# Sallen_key_bandpass.net
KiCad netlist of a schematic drawn in Altium Designer
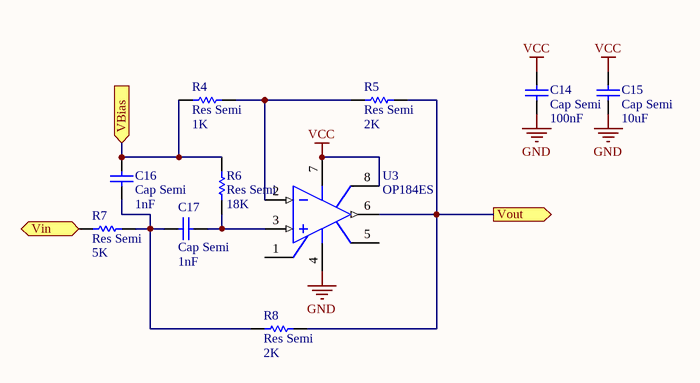
[diagram p0: Sallen_key_bandpass.SchDoc]

(export (version "E")
  (design (tool "Eeschema 10.0.6"))
  (components
    (comp (ref "C14")
      (value "Cap Semi")
      (footprint "C0805")
      (description "Capacitor (Semiconductor SIM Model)")
      (fields (field (name "ALTIUM_VALUE") "100nF") (field (name "PUBLISHER") "Altium Limited"))
      (libsource (lib "Miscellaneous Devices") (part "Cap Semi"))
    )
    (comp (ref "C15")
      (value "Cap Semi")
      (footprint "C1206")
      (description "Capacitor (Semiconductor SIM Model)")
      (fields (field (name "ALTIUM_VALUE") "10uF") (field (name "PUBLISHER") "Altium Limited"))
      (libsource (lib "Miscellaneous Devices") (part "Cap Semi"))
    )
    (comp (ref "C16")
      (value "Cap Semi")
      (footprint "C0805")
      (description "Capacitor (Semiconductor SIM Model)")
      (fields (field (name "ALTIUM_VALUE") "1nF") (field (name "PUBLISHER") "Altium Limited"))
      (libsource (lib "Miscellaneous Devices") (part "Cap Semi"))
    )
    (comp (ref "C17")
      (value "Cap Semi")
      (footprint "C0805")
      (description "Capacitor (Semiconductor SIM Model)")
      (fields (field (name "ALTIUM_VALUE") "1nF") (field (name "PUBLISHER") "Altium Limited"))
      (libsource (lib "Miscellaneous Devices") (part "Cap Semi"))
    )
    (comp (ref "R4")
      (value "Res Semi")
      (footprint "6-0805_M")
      (description "Semiconductor Resistor")
      (fields (field (name "ALTIUM_VALUE") "1K") (field (name "PUBLISHER") "Altium Limited"))
      (libsource (lib "Miscellaneous Devices") (part "Res Semi"))
    )
    (comp (ref "R5")
      (value "Res Semi")
      (footprint "6-0805_M")
      (description "Semiconductor Resistor")
      (fields (field (name "ALTIUM_VALUE") "2K") (field (name "PUBLISHER") "Altium Limited"))
      (libsource (lib "Miscellaneous Devices") (part "Res Semi"))
    )
    (comp (ref "R6")
      (value "Res Semi")
      (footprint "6-0805_M")
      (description "Semiconductor Resistor")
      (fields (field (name "ALTIUM_VALUE") "18K") (field (name "PUBLISHER") "Altium Limited"))
      (libsource (lib "Miscellaneous Devices") (part "Res Semi"))
    )
    (comp (ref "R7")
      (value "Res Semi")
      (footprint "6-0805_M")
      (description "Semiconductor Resistor")
      (fields (field (name "ALTIUM_VALUE") "5K") (field (name "PUBLISHER") "Altium Limited"))
      (libsource (lib "Miscellaneous Devices") (part "Res Semi"))
    )
    (comp (ref "R8")
      (value "Res Semi")
      (footprint "6-0805_M")
      (description "Semiconductor Resistor")
      (fields (field (name "ALTIUM_VALUE") "2K") (field (name "PUBLISHER") "Altium Limited"))
      (libsource (lib "Miscellaneous Devices") (part "Res Semi"))
    )
    (comp (ref "U3")
      (value "OP184ES")
      (footprint "SO-8")
      (description "Precision Rail-to-Rail Input and Ouput Operational Amplifier")
      (fields (field (name "PUBLISHER") "Altium Limited"))
      (libsource (lib "AD Operational Amplifier") (part "OP184ES"))
    )
  )
  (nets
    (net (code "1") (name "/VBias") (class "Default")
      (node (ref "C16") (pin "2") (pinfunction "2_2") (pintype "passive"))
      (node (ref "R4") (pin "1") (pinfunction "1_1") (pintype "passive"))
      (node (ref "R6") (pin "2") (pinfunction "2_2") (pintype "passive"))
    )
    (net (code "2") (name "/Vin") (class "Default")
      (node (ref "R7") (pin "1") (pinfunction "1_1") (pintype "passive"))
    )
    (net (code "3") (name "/Vout") (class "Default")
      (node (ref "R5") (pin "2") (pinfunction "2_2") (pintype "passive"))
      (node (ref "R8") (pin "2") (pinfunction "2_2") (pintype "passive"))
      (node (ref "U3") (pin "6") (pinfunction "OUT_6") (pintype "output"))
    )
    (net (code "4") (name "GND") (class "Default")
      (node (ref "C14") (pin "1") (pinfunction "1_1") (pintype "passive"))
      (node (ref "C15") (pin "1") (pinfunction "1_1") (pintype "passive"))
      (node (ref "U3") (pin "4") (pinfunction "V-_4") (pintype "power_in"))
    )
    (net (code "5") (name "Net-(C16-Pad1)") (class "Default")
      (node (ref "C16") (pin "1") (pinfunction "1_1") (pintype "passive"))
      (node (ref "C17") (pin "2") (pinfunction "2_2") (pintype "passive"))
      (node (ref "R7") (pin "2") (pinfunction "2_2") (pintype "passive"))
      (node (ref "R8") (pin "1") (pinfunction "1_1") (pintype "passive"))
    )
    (net (code "6") (name "Net-(U3-IN+)") (class "Default")
      (node (ref "C17") (pin "1") (pinfunction "1_1") (pintype "passive"))
      (node (ref "R6") (pin "1") (pinfunction "1_1") (pintype "passive"))
      (node (ref "U3") (pin "3") (pinfunction "IN+_3") (pintype "input"))
    )
    (net (code "7") (name "Net-(U3-IN-)") (class "Default")
      (node (ref "R4") (pin "2") (pinfunction "2_2") (pintype "passive"))
      (node (ref "R5") (pin "1") (pinfunction "1_1") (pintype "passive"))
      (node (ref "U3") (pin "2") (pinfunction "IN-_2") (pintype "input"))
    )
    (net (code "8") (name "VCC") (class "Default")
      (node (ref "C14") (pin "2") (pinfunction "2_2") (pintype "passive"))
      (node (ref "C15") (pin "2") (pinfunction "2_2") (pintype "passive"))
      (node (ref "U3") (pin "7") (pinfunction "V+_7") (pintype "power_in"))
      (node (ref "U3") (pin "8") (pinfunction "NC_8") (pintype "passive"))
    )
    (net (code "9") (name "unconnected-(U3-NUL-Pad1)") (class "Default")
      (node (ref "U3") (pin "1") (pinfunction "NUL_1") (pintype "passive"))
    )
    (net (code "10") (name "unconnected-(U3-NUL-Pad5)") (class "Default")
      (node (ref "U3") (pin "5") (pinfunction "NUL_5") (pintype "passive"))
    )
  )
)
